# tinyups.net
KiCad netlist of a schematic drawn in EAGLE
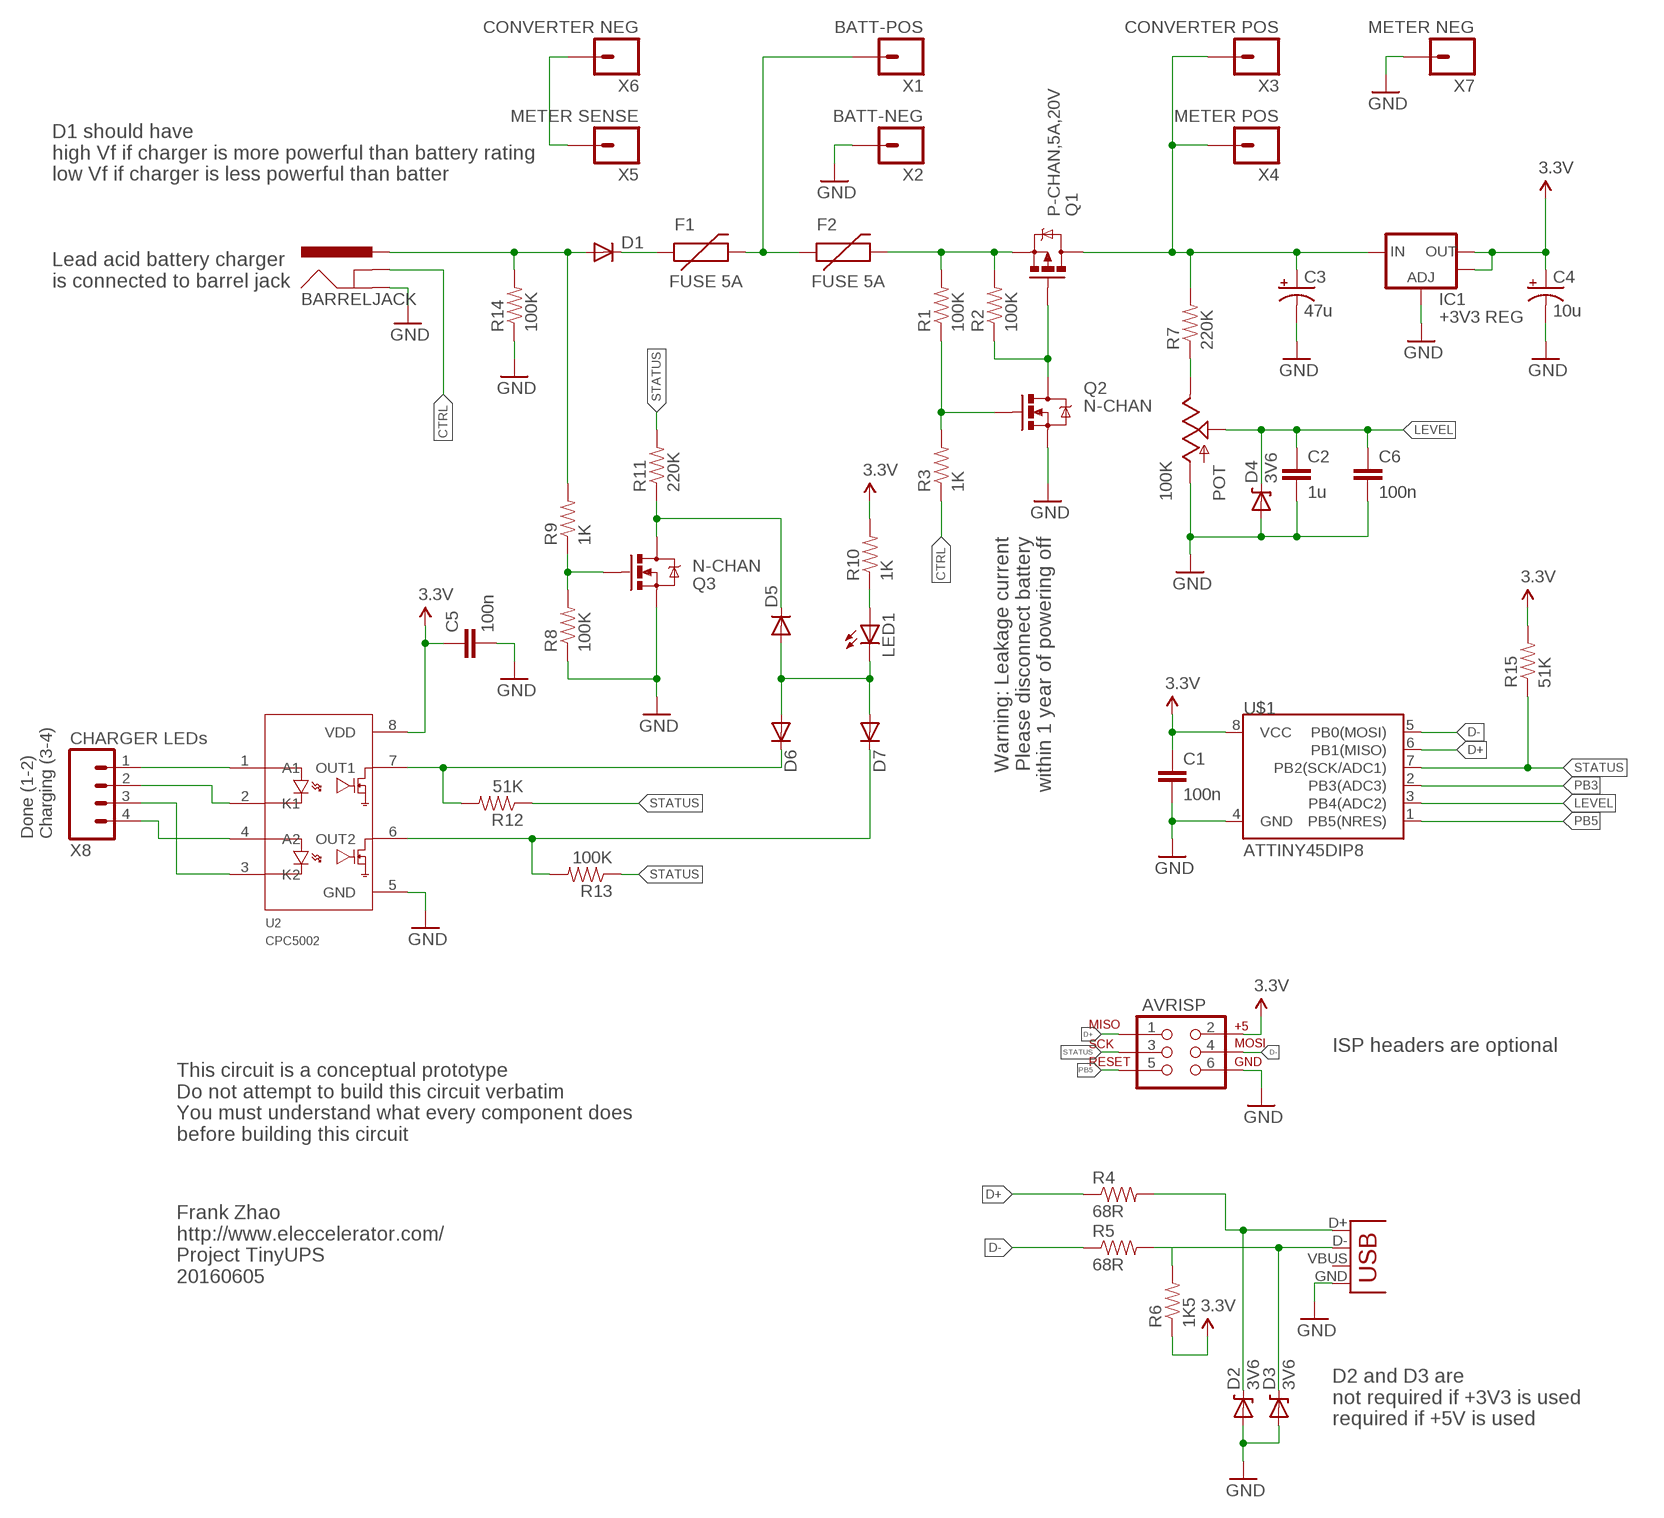
[diagram p0: schematic, sheet 1]

(export (version "E")
  (design (tool "Eeschema 10.0.6"))
  (components
    (comp (ref "AVRISP")
      (value "AVR_SPI_PRG_6NS")
      (footprint "eagle-import:2X3-NS")
      (libsource (lib "eagle-import") (part "AVR_SPI_PRG_6NS"))
    )
    (comp (ref "BARRELJACK")
      (value "POWER_JACK-LO-PROFILE")
      (footprint "eagle-import:DC-BARREL-JACK-LO-PROFILE")
      (libsource (lib "eagle-import") (part "POWER_JACK-LO-PROFILE"))
    )
    (comp (ref "C1")
      (value "100n")
      (footprint "eagle-import:0603-CAP")
      (libsource (lib "eagle-import") (part "CAP0603-CAP"))
    )
    (comp (ref "C2")
      (value "1u")
      (footprint "eagle-import:0603-CAP")
      (libsource (lib "eagle-import") (part "CAP0603-CAP"))
    )
    (comp (ref "C3")
      (value "47u")
      (footprint "eagle-import:EIA3216")
      (libsource (lib "eagle-import") (part "CAP_POL1206"))
    )
    (comp (ref "C4")
      (value "10u")
      (footprint "eagle-import:EIA3216")
      (libsource (lib "eagle-import") (part "CAP_POL1206"))
    )
    (comp (ref "C5")
      (value "100n")
      (footprint "eagle-import:0603-CAP")
      (libsource (lib "eagle-import") (part "CAP0603-CAP"))
    )
    (comp (ref "C6")
      (value "100n")
      (footprint "eagle-import:0603-CAP")
      (libsource (lib "eagle-import") (part "CAP0603-CAP"))
    )
    (comp (ref "D1")
      (value "DIODE1N4148")
      (footprint "eagle-import:DIODE-1N4148")
      (libsource (lib "eagle-import") (part "DIODE1N4148"))
    )
    (comp (ref "D2")
      (value "3V6")
      (footprint "eagle-import:SOD-323")
      (libsource (lib "eagle-import") (part "DIODE-ZENER-BZT52"))
    )
    (comp (ref "D3")
      (value "3V6")
      (footprint "eagle-import:SOD-323")
      (libsource (lib "eagle-import") (part "DIODE-ZENER-BZT52"))
    )
    (comp (ref "D4")
      (value "3V6")
      (footprint "eagle-import:SOD-323")
      (libsource (lib "eagle-import") (part "DIODE-ZENER-BZT52"))
    )
    (comp (ref "D5")
      (value "DIODESOD")
      (footprint "eagle-import:SOD-323")
      (libsource (lib "eagle-import") (part "DIODESOD"))
    )
    (comp (ref "D6")
      (value "DIODESOD")
      (footprint "eagle-import:SOD-323")
      (libsource (lib "eagle-import") (part "DIODESOD"))
    )
    (comp (ref "D7")
      (value "DIODESOD")
      (footprint "eagle-import:SOD-323")
      (libsource (lib "eagle-import") (part "DIODESOD"))
    )
    (comp (ref "F1")
      (value "FUSE 5A")
      (footprint "eagle-import:PTC")
      (libsource (lib "eagle-import") (part "PTCPTH"))
    )
    (comp (ref "F2")
      (value "FUSE 5A")
      (footprint "eagle-import:PTC")
      (libsource (lib "eagle-import") (part "PTCPTH"))
    )
    (comp (ref "IC1")
      (value "+3V3 REG")
      (footprint "eagle-import:SOT223")
      (libsource (lib "eagle-import") (part "V_REG_LM1117SOT223"))
    )
    (comp (ref "LED1")
      (value "LED3MM")
      (footprint "eagle-import:LED3MM")
      (libsource (lib "eagle-import") (part "LED3MM"))
    )
    (comp (ref "POT")
      (value "100K")
      (footprint "eagle-import:POT-MODEL89")
      (libsource (lib "eagle-import") (part "POT-MODEL89"))
    )
    (comp (ref "Q1")
      (value "P-CHAN,5A,20V")
      (footprint "eagle-import:TO220V")
      (libsource (lib "eagle-import") (part "MOSFET-PCHANNEL-TO220V"))
    )
    (comp (ref "Q2")
      (value "N-CHAN")
      (footprint "eagle-import:SOT23-3")
      (libsource (lib "eagle-import") (part "MOSFET-NCHANNELSMD"))
    )
    (comp (ref "Q3")
      (value "N-CHAN")
      (footprint "eagle-import:SOT23-3")
      (libsource (lib "eagle-import") (part "MOSFET-NCHANNELSMD"))
    )
    (comp (ref "R1")
      (value "100K")
      (footprint "eagle-import:0603-RES")
      (libsource (lib "eagle-import") (part "RESISTOR0603-RES"))
    )
    (comp (ref "R2")
      (value "100K")
      (footprint "eagle-import:0603-RES")
      (libsource (lib "eagle-import") (part "RESISTOR0603-RES"))
    )
    (comp (ref "R3")
      (value "1K")
      (footprint "eagle-import:0603-RES")
      (libsource (lib "eagle-import") (part "RESISTOR0603-RES"))
    )
    (comp (ref "R4")
      (value "68R")
      (footprint "eagle-import:0603-RES")
      (libsource (lib "eagle-import") (part "RESISTOR0603-RES"))
    )
    (comp (ref "R5")
      (value "68R")
      (footprint "eagle-import:0603-RES")
      (libsource (lib "eagle-import") (part "RESISTOR0603-RES"))
    )
    (comp (ref "R6")
      (value "1K5")
      (footprint "eagle-import:0603-RES")
      (libsource (lib "eagle-import") (part "RESISTOR0603-RES"))
    )
    (comp (ref "R7")
      (value "220K")
      (footprint "eagle-import:0603-RES")
      (libsource (lib "eagle-import") (part "RESISTOR0603-RES"))
    )
    (comp (ref "R8")
      (value "100K")
      (footprint "eagle-import:0603-RES")
      (libsource (lib "eagle-import") (part "RESISTOR0603-RES"))
    )
    (comp (ref "R9")
      (value "1K")
      (footprint "eagle-import:0603-RES")
      (libsource (lib "eagle-import") (part "RESISTOR0603-RES"))
    )
    (comp (ref "R10")
      (value "1K")
      (footprint "eagle-import:0603-RES")
      (libsource (lib "eagle-import") (part "RESISTOR0603-RES"))
    )
    (comp (ref "R11")
      (value "220K")
      (footprint "eagle-import:0603-RES")
      (libsource (lib "eagle-import") (part "RESISTOR0603-RES"))
    )
    (comp (ref "R12")
      (value "51K")
      (footprint "eagle-import:0603-RES")
      (libsource (lib "eagle-import") (part "RESISTOR0603-RES"))
    )
    (comp (ref "R13")
      (value "100K")
      (footprint "eagle-import:0603-RES")
      (libsource (lib "eagle-import") (part "RESISTOR0603-RES"))
    )
    (comp (ref "R14")
      (value "100K")
      (footprint "eagle-import:0603-RES")
      (libsource (lib "eagle-import") (part "RESISTOR0603-RES"))
    )
    (comp (ref "R15")
      (value "51K")
      (footprint "eagle-import:0603-RES")
      (libsource (lib "eagle-import") (part "RESISTOR0603-RES"))
    )
    (comp (ref "U$1")
      (value "ATTINY45DIP8")
      (footprint "eagle-import:DIP08")
      (libsource (lib "eagle-import") (part "ATTINY45DIP8"))
    )
    (comp (ref "U2")
      (value "CPC5002")
      (footprint "eagle-import:OPTOISOLATOR-DIPSMD-8")
      (libsource (lib "eagle-import") (part "OPTOISOLATOR-CPC5002"))
    )
    (comp (ref "USB")
      (value "USB-MB-H")
      (footprint "eagle-import:USB-MB-H")
      (libsource (lib "eagle-import") (part "USB-MB-H"))
    )
    (comp (ref "X1")
      (value "BATT-POS")
      (footprint "eagle-import:1X01")
      (libsource (lib "eagle-import") (part "M01PTH"))
    )
    (comp (ref "X2")
      (value "BATT-NEG")
      (footprint "eagle-import:1X01")
      (libsource (lib "eagle-import") (part "M01PTH"))
    )
    (comp (ref "X3")
      (value "CONVERTER POS")
      (footprint "eagle-import:1X01")
      (libsource (lib "eagle-import") (part "M01PTH"))
    )
    (comp (ref "X4")
      (value "METER POS")
      (footprint "eagle-import:1X01")
      (libsource (lib "eagle-import") (part "M01PTH"))
    )
    (comp (ref "X5")
      (value "METER SENSE")
      (footprint "eagle-import:1X01")
      (libsource (lib "eagle-import") (part "M01PTH"))
    )
    (comp (ref "X6")
      (value "CONVERTER NEG")
      (footprint "eagle-import:1X01")
      (libsource (lib "eagle-import") (part "M01PTH"))
    )
    (comp (ref "X7")
      (value "METER NEG")
      (footprint "eagle-import:1X01")
      (libsource (lib "eagle-import") (part "M01PTH"))
    )
    (comp (ref "X8")
      (value "CHARGER LEDs")
      (footprint "eagle-import:1X04")
      (libsource (lib "eagle-import") (part "M04PTH"))
    )
  )
  (nets
    (net (code "1") (name "3.3V") (class "Default")
      (node (ref "AVRISP") (pin "2") (pinfunction "2_2") (pintype "passive"))
      (node (ref "C1") (pin "1") (pinfunction "1_1") (pintype "passive"))
      (node (ref "C4") (pin "A") (pinfunction "+_A") (pintype "passive"))
      (node (ref "C5") (pin "1") (pinfunction "1_1") (pintype "passive"))
      (node (ref "IC1") (pin "2") (pinfunction "OUT_2") (pintype "output"))
      (node (ref "IC1") (pin "4") (pinfunction "OUT_4") (pintype "output"))
      (node (ref "R10") (pin "2") (pinfunction "2_2") (pintype "passive"))
      (node (ref "R15") (pin "2") (pinfunction "2_2") (pintype "passive"))
      (node (ref "R6") (pin "1") (pinfunction "1_1") (pintype "passive"))
      (node (ref "U$1") (pin "8") (pinfunction "VCC_8") (pintype "bidirectional"))
      (node (ref "U2") (pin "8") (pinfunction "VDD_8") (pintype "bidirectional"))
    )
    (net (code "2") (name "CTRL") (class "Default")
      (node (ref "BARRELJACK") (pin "3") (pinfunction "GNDBREAK_3") (pintype "bidirectional"))
      (node (ref "R3") (pin "1") (pinfunction "1_1") (pintype "passive"))
    )
    (net (code "3") (name "D+") (class "Default")
      (node (ref "AVRISP") (pin "1") (pinfunction "1_1") (pintype "passive"))
      (node (ref "R4") (pin "1") (pinfunction "1_1") (pintype "passive"))
      (node (ref "U$1") (pin "6") (pinfunction "PB1(MISO)_6") (pintype "bidirectional"))
    )
    (net (code "4") (name "D-") (class "Default")
      (node (ref "AVRISP") (pin "4") (pinfunction "4_4") (pintype "passive"))
      (node (ref "R5") (pin "1") (pinfunction "1_1") (pintype "passive"))
      (node (ref "U$1") (pin "5") (pinfunction "PB0(MOSI)_5") (pintype "bidirectional"))
    )
    (net (code "5") (name "GND") (class "Default")
      (node (ref "AVRISP") (pin "6") (pinfunction "6_6") (pintype "passive"))
      (node (ref "BARRELJACK") (pin "2") (pinfunction "GND_2") (pintype "bidirectional"))
      (node (ref "C1") (pin "2") (pinfunction "2_2") (pintype "passive"))
      (node (ref "C2") (pin "2") (pinfunction "2_2") (pintype "passive"))
      (node (ref "C3") (pin "C") (pinfunction "-_C") (pintype "passive"))
      (node (ref "C4") (pin "C") (pinfunction "-_C") (pintype "passive"))
      (node (ref "C5") (pin "2") (pinfunction "2_2") (pintype "passive"))
      (node (ref "C6") (pin "2") (pinfunction "2_2") (pintype "passive"))
      (node (ref "D2") (pin "2") (pinfunction "A_2") (pintype "passive"))
      (node (ref "D3") (pin "2") (pinfunction "A_2") (pintype "passive"))
      (node (ref "D4") (pin "2") (pinfunction "A_2") (pintype "passive"))
      (node (ref "IC1") (pin "1") (pinfunction "ADJ_1") (pintype "input"))
      (node (ref "POT") (pin "3") (pinfunction "A_3") (pintype "passive"))
      (node (ref "Q2") (pin "2") (pinfunction "S_2") (pintype "passive"))
      (node (ref "Q3") (pin "2") (pinfunction "S_2") (pintype "passive"))
      (node (ref "R14") (pin "1") (pinfunction "1_1") (pintype "passive"))
      (node (ref "R8") (pin "1") (pinfunction "1_1") (pintype "passive"))
      (node (ref "U$1") (pin "4") (pinfunction "GND_4") (pintype "bidirectional"))
      (node (ref "U2") (pin "5") (pinfunction "GND_5") (pintype "bidirectional"))
      (node (ref "USB") (pin "GND") (pinfunction "GND_GND") (pintype "bidirectional"))
      (node (ref "X2") (pin "1") (pinfunction "1_1") (pintype "passive"))
      (node (ref "X7") (pin "1") (pinfunction "1_1") (pintype "passive"))
    )
    (net (code "6") (name "LEVEL") (class "Default")
      (node (ref "C2") (pin "1") (pinfunction "1_1") (pintype "passive"))
      (node (ref "C6") (pin "1") (pinfunction "1_1") (pintype "passive"))
      (node (ref "D4") (pin "1") (pinfunction "C_1") (pintype "passive"))
      (node (ref "POT") (pin "W") (pinfunction "S_W") (pintype "passive"))
      (node (ref "U$1") (pin "3") (pinfunction "PB4(ADC2)_3") (pintype "bidirectional"))
    )
    (net (code "7") (name "Net-(BARRELJACK-PWR)") (class "Default")
      (node (ref "BARRELJACK") (pin "1") (pinfunction "PWR_1") (pintype "bidirectional"))
      (node (ref "D1") (pin "A") (pinfunction "A_A") (pintype "passive"))
      (node (ref "R14") (pin "2") (pinfunction "2_2") (pintype "passive"))
      (node (ref "R9") (pin "2") (pinfunction "2_2") (pintype "passive"))
    )
    (net (code "8") (name "Net-(C3-+)") (class "Default")
      (node (ref "C3") (pin "A") (pinfunction "+_A") (pintype "passive"))
      (node (ref "IC1") (pin "3") (pinfunction "IN_3") (pintype "input"))
      (node (ref "Q1") (pin "2") (pinfunction "D_2") (pintype "passive"))
      (node (ref "R7") (pin "2") (pinfunction "2_2") (pintype "passive"))
      (node (ref "X3") (pin "1") (pinfunction "1_1") (pintype "passive"))
      (node (ref "X4") (pin "1") (pinfunction "1_1") (pintype "passive"))
    )
    (net (code "9") (name "Net-(D2-C)") (class "Default")
      (node (ref "D2") (pin "1") (pinfunction "C_1") (pintype "passive"))
      (node (ref "R4") (pin "2") (pinfunction "2_2") (pintype "passive"))
      (node (ref "USB") (pin "D+") (pinfunction "D+_D+") (pintype "bidirectional"))
    )
    (net (code "10") (name "Net-(D3-C)") (class "Default")
      (node (ref "D3") (pin "1") (pinfunction "C_1") (pintype "passive"))
      (node (ref "R5") (pin "2") (pinfunction "2_2") (pintype "passive"))
      (node (ref "R6") (pin "2") (pinfunction "2_2") (pintype "passive"))
      (node (ref "USB") (pin "D-") (pinfunction "D-_D-") (pintype "bidirectional"))
    )
    (net (code "11") (name "Net-(D5-A)") (class "Default")
      (node (ref "D5") (pin "2") (pinfunction "A_2") (pintype "passive"))
      (node (ref "D6") (pin "2") (pinfunction "A_2") (pintype "passive"))
      (node (ref "D7") (pin "2") (pinfunction "A_2") (pintype "passive"))
      (node (ref "LED1") (pin "K") (pinfunction "C_K") (pintype "passive"))
    )
    (net (code "12") (name "Net-(D5-C)") (class "Default")
      (node (ref "D5") (pin "1") (pinfunction "C_1") (pintype "passive"))
      (node (ref "Q3") (pin "3") (pinfunction "D_3") (pintype "passive"))
      (node (ref "R11") (pin "1") (pinfunction "1_1") (pintype "passive"))
    )
    (net (code "13") (name "Net-(D6-C)") (class "Default")
      (node (ref "D6") (pin "1") (pinfunction "C_1") (pintype "passive"))
      (node (ref "R12") (pin "2") (pinfunction "2_2") (pintype "passive"))
      (node (ref "U2") (pin "7") (pinfunction "OUT1_7") (pintype "open_collector"))
    )
    (net (code "14") (name "Net-(D7-C)") (class "Default")
      (node (ref "D7") (pin "1") (pinfunction "C_1") (pintype "passive"))
      (node (ref "R13") (pin "2") (pinfunction "2_2") (pintype "passive"))
      (node (ref "U2") (pin "6") (pinfunction "OUT2_6") (pintype "open_collector"))
    )
    (net (code "15") (name "Net-(F1-1)") (class "Default")
      (node (ref "D1") (pin "C") (pinfunction "C_C") (pintype "passive"))
      (node (ref "F1") (pin "P$1") (pinfunction "1_P$1") (pintype "bidirectional"))
    )
    (net (code "16") (name "Net-(F1-2)") (class "Default")
      (node (ref "F1") (pin "P$2") (pinfunction "2_P$2") (pintype "bidirectional"))
      (node (ref "F2") (pin "P$1") (pinfunction "1_P$1") (pintype "bidirectional"))
      (node (ref "X1") (pin "1") (pinfunction "1_1") (pintype "passive"))
    )
    (net (code "17") (name "Net-(F2-2)") (class "Default")
      (node (ref "F2") (pin "P$2") (pinfunction "2_P$2") (pintype "bidirectional"))
      (node (ref "Q1") (pin "3") (pinfunction "S_3") (pintype "passive"))
      (node (ref "R1") (pin "2") (pinfunction "2_2") (pintype "passive"))
      (node (ref "R2") (pin "2") (pinfunction "2_2") (pintype "passive"))
    )
    (net (code "18") (name "Net-(LED1-PadA)") (class "Default")
      (node (ref "LED1") (pin "A") (pinfunction "A_A") (pintype "passive"))
      (node (ref "R10") (pin "1") (pinfunction "1_1") (pintype "passive"))
    )
    (net (code "19") (name "Net-(POT-E)") (class "Default")
      (node (ref "POT") (pin "1") (pinfunction "E_1") (pintype "passive"))
      (node (ref "R7") (pin "1") (pinfunction "1_1") (pintype "passive"))
    )
    (net (code "20") (name "Net-(Q1-G)") (class "Default")
      (node (ref "Q1") (pin "1") (pinfunction "G_1") (pintype "passive"))
      (node (ref "Q2") (pin "3") (pinfunction "D_3") (pintype "passive"))
      (node (ref "R2") (pin "1") (pinfunction "1_1") (pintype "passive"))
    )
    (net (code "21") (name "Net-(Q2-G)") (class "Default")
      (node (ref "Q2") (pin "1") (pinfunction "G_1") (pintype "passive"))
      (node (ref "R1") (pin "1") (pinfunction "1_1") (pintype "passive"))
      (node (ref "R3") (pin "2") (pinfunction "2_2") (pintype "passive"))
    )
    (net (code "22") (name "Net-(Q3-G)") (class "Default")
      (node (ref "Q3") (pin "1") (pinfunction "G_1") (pintype "passive"))
      (node (ref "R8") (pin "2") (pinfunction "2_2") (pintype "passive"))
      (node (ref "R9") (pin "1") (pinfunction "1_1") (pintype "passive"))
    )
    (net (code "23") (name "Net-(U2-A1)") (class "Default")
      (node (ref "U2") (pin "1") (pinfunction "A1_1") (pintype "bidirectional"))
      (node (ref "X8") (pin "1") (pinfunction "1_1") (pintype "passive"))
    )
    (net (code "24") (name "Net-(U2-A2)") (class "Default")
      (node (ref "U2") (pin "4") (pinfunction "A2_4") (pintype "bidirectional"))
      (node (ref "X8") (pin "4") (pinfunction "4_4") (pintype "passive"))
    )
    (net (code "25") (name "Net-(U2-K1)") (class "Default")
      (node (ref "U2") (pin "2") (pinfunction "K1_2") (pintype "bidirectional"))
      (node (ref "X8") (pin "2") (pinfunction "2_2") (pintype "passive"))
    )
    (net (code "26") (name "Net-(U2-K2)") (class "Default")
      (node (ref "U2") (pin "3") (pinfunction "K2_3") (pintype "bidirectional"))
      (node (ref "X8") (pin "3") (pinfunction "3_3") (pintype "passive"))
    )
    (net (code "27") (name "Net-(X5-Pad1)") (class "Default")
      (node (ref "X5") (pin "1") (pinfunction "1_1") (pintype "passive"))
      (node (ref "X6") (pin "1") (pinfunction "1_1") (pintype "passive"))
    )
    (net (code "28") (name "PB3") (class "Default")
      (node (ref "U$1") (pin "2") (pinfunction "PB3(ADC3)_2") (pintype "bidirectional"))
    )
    (net (code "29") (name "PB5") (class "Default")
      (node (ref "AVRISP") (pin "5") (pinfunction "5_5") (pintype "passive"))
      (node (ref "U$1") (pin "1") (pinfunction "PB5(NRES)_1") (pintype "bidirectional"))
    )
    (net (code "30") (name "STATUS") (class "Default")
      (node (ref "AVRISP") (pin "3") (pinfunction "3_3") (pintype "passive"))
      (node (ref "R11") (pin "2") (pinfunction "2_2") (pintype "passive"))
      (node (ref "R12") (pin "1") (pinfunction "1_1") (pintype "passive"))
      (node (ref "R13") (pin "1") (pinfunction "1_1") (pintype "passive"))
      (node (ref "R15") (pin "1") (pinfunction "1_1") (pintype "passive"))
      (node (ref "U$1") (pin "7") (pinfunction "PB2(SCK/ADC1)_7") (pintype "bidirectional"))
    )
    (net (code "31") (name "unconnected-(USB-PadVBUS)") (class "Default")
      (node (ref "USB") (pin "VBUS") (pinfunction "VBUS_VBUS") (pintype "bidirectional"))
    )
  )
)
